# digital_sensor.net
KiCad netlist of a schematic drawn in EAGLE
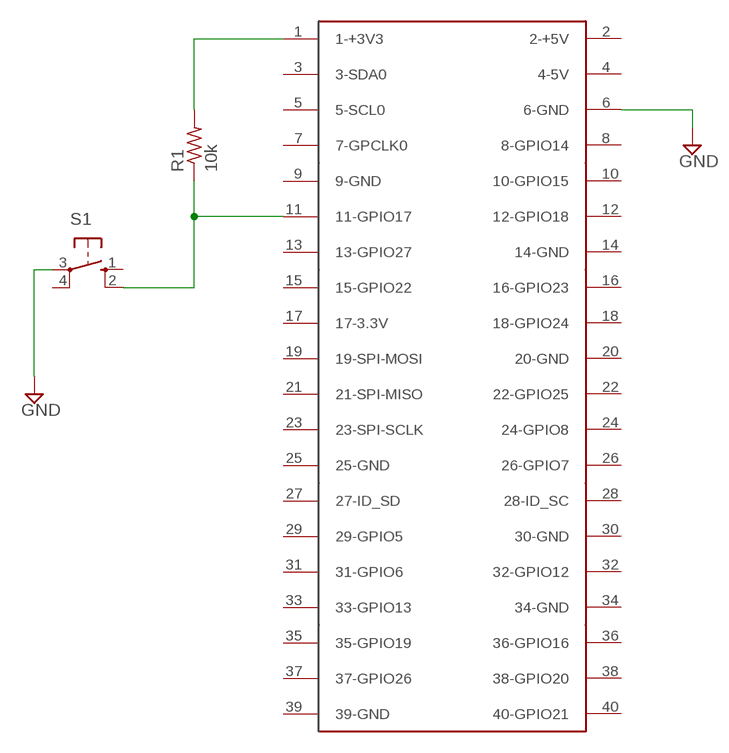
[diagram p0: schematic, sheet 1]

(export (version "E")
  (design (tool "Eeschema 10.0.6"))
  (components
    (comp (ref "R1")
      (value "10k")
      (footprint "eagle-import:0207_12")
      (libsource (lib "eagle-import") (part "R-US_0207/12"))
    )
    (comp (ref "S1")
      (value "40-XX-ROUND")
      (footprint "eagle-import:B3F-40XX-ROUND")
      (libsource (lib "eagle-import") (part "40-XX-ROUND"))
    )
    (comp (ref "U$1")
      (value "RASPBERRY-PI")
      (footprint "eagle-import:RASPBERRY-PI")
      (libsource (lib "eagle-import") (part "RASPBERRY-PI"))
    )
  )
  (nets
    (net (code "1") (name "GND") (class "Default")
      (node (ref "S1") (pin "3") (pinfunction "P_3") (pintype "passive"))
      (node (ref "U$1") (pin "6") (pinfunction "6-GND_6") (pintype "bidirectional"))
    )
    (net (code "2") (name "Net-(S1-S1)") (class "Default")
      (node (ref "R1") (pin "1") (pinfunction "1_1") (pintype "passive"))
      (node (ref "S1") (pin "2") (pinfunction "S1_2") (pintype "passive"))
      (node (ref "U$1") (pin "11") (pinfunction "11-GPIO17_11") (pintype "bidirectional"))
    )
    (net (code "3") (name "Net-(U$1-1-+3V3)") (class "Default")
      (node (ref "R1") (pin "2") (pinfunction "2_2") (pintype "passive"))
      (node (ref "U$1") (pin "1") (pinfunction "1-+3V3_1") (pintype "bidirectional"))
    )
    (net (code "4") (name "unconnected-(S1-P1-Pad4)") (class "Default")
      (node (ref "S1") (pin "4") (pinfunction "P1_4") (pintype "passive"))
    )
    (net (code "5") (name "unconnected-(S1-S-Pad1)") (class "Default")
      (node (ref "S1") (pin "1") (pinfunction "S_1") (pintype "passive"))
    )
    (net (code "6") (name "unconnected-(U$1-2-+5V-Pad2)") (class "Default")
      (node (ref "U$1") (pin "2") (pinfunction "2-+5V_2") (pintype "bidirectional"))
    )
    (net (code "7") (name "unconnected-(U$1-3-SDA0-Pad3)") (class "Default")
      (node (ref "U$1") (pin "3") (pinfunction "3-SDA0_3") (pintype "bidirectional"))
    )
    (net (code "8") (name "unconnected-(U$1-4-5V-Pad4)") (class "Default")
      (node (ref "U$1") (pin "4") (pinfunction "4-5V_4") (pintype "bidirectional"))
    )
    (net (code "9") (name "unconnected-(U$1-5-SCL0-Pad5)") (class "Default")
      (node (ref "U$1") (pin "5") (pinfunction "5-SCL0_5") (pintype "bidirectional"))
    )
    (net (code "10") (name "unconnected-(U$1-7-GPCLK0-Pad7)") (class "Default")
      (node (ref "U$1") (pin "7") (pinfunction "7-GPCLK0_7") (pintype "bidirectional"))
    )
    (net (code "11") (name "unconnected-(U$1-8-GPIO14-Pad8)") (class "Default")
      (node (ref "U$1") (pin "8") (pinfunction "8-GPIO14_8") (pintype "bidirectional"))
    )
    (net (code "12") (name "unconnected-(U$1-9-GND-Pad9)") (class "Default")
      (node (ref "U$1") (pin "9") (pinfunction "9-GND_9") (pintype "bidirectional"))
    )
    (net (code "13") (name "unconnected-(U$1-10-GPIO15-Pad10)") (class "Default")
      (node (ref "U$1") (pin "10") (pinfunction "10-GPIO15_10") (pintype "bidirectional"))
    )
    (net (code "14") (name "unconnected-(U$1-12-GPIO18-Pad12)") (class "Default")
      (node (ref "U$1") (pin "12") (pinfunction "12-GPIO18_12") (pintype "bidirectional"))
    )
    (net (code "15") (name "unconnected-(U$1-13-GPIO27-Pad13)") (class "Default")
      (node (ref "U$1") (pin "13") (pinfunction "13-GPIO27_13") (pintype "bidirectional"))
    )
    (net (code "16") (name "unconnected-(U$1-14-GND-Pad14)") (class "Default")
      (node (ref "U$1") (pin "14") (pinfunction "14-GND_14") (pintype "bidirectional"))
    )
    (net (code "17") (name "unconnected-(U$1-15-GPIO22-Pad15)") (class "Default")
      (node (ref "U$1") (pin "15") (pinfunction "15-GPIO22_15") (pintype "bidirectional"))
    )
    (net (code "18") (name "unconnected-(U$1-16-GPIO23-Pad16)") (class "Default")
      (node (ref "U$1") (pin "16") (pinfunction "16-GPIO23_16") (pintype "bidirectional"))
    )
    (net (code "19") (name "unconnected-(U$1-17-3.3V-Pad17)") (class "Default")
      (node (ref "U$1") (pin "17") (pinfunction "17-3.3V_17") (pintype "bidirectional"))
    )
    (net (code "20") (name "unconnected-(U$1-18-GPIO24-Pad18)") (class "Default")
      (node (ref "U$1") (pin "18") (pinfunction "18-GPIO24_18") (pintype "bidirectional"))
    )
    (net (code "21") (name "unconnected-(U$1-19-SPI-MOSI-Pad19)") (class "Default")
      (node (ref "U$1") (pin "19") (pinfunction "19-SPI-MOSI_19") (pintype "bidirectional"))
    )
    (net (code "22") (name "unconnected-(U$1-20-GND-Pad20)") (class "Default")
      (node (ref "U$1") (pin "20") (pinfunction "20-GND_20") (pintype "bidirectional"))
    )
    (net (code "23") (name "unconnected-(U$1-21-SPI-MISO-Pad21)") (class "Default")
      (node (ref "U$1") (pin "21") (pinfunction "21-SPI-MISO_21") (pintype "bidirectional"))
    )
    (net (code "24") (name "unconnected-(U$1-22-GPIO25-Pad22)") (class "Default")
      (node (ref "U$1") (pin "22") (pinfunction "22-GPIO25_22") (pintype "bidirectional"))
    )
    (net (code "25") (name "unconnected-(U$1-23-SPI-SCLK-Pad23)") (class "Default")
      (node (ref "U$1") (pin "23") (pinfunction "23-SPI-SCLK_23") (pintype "bidirectional"))
    )
    (net (code "26") (name "unconnected-(U$1-24-GPIO8-Pad24)") (class "Default")
      (node (ref "U$1") (pin "24") (pinfunction "24-GPIO8_24") (pintype "bidirectional"))
    )
    (net (code "27") (name "unconnected-(U$1-25-GND-Pad25)") (class "Default")
      (node (ref "U$1") (pin "25") (pinfunction "25-GND_25") (pintype "bidirectional"))
    )
    (net (code "28") (name "unconnected-(U$1-26-GPIO7-Pad26)") (class "Default")
      (node (ref "U$1") (pin "26") (pinfunction "26-GPIO7_26") (pintype "bidirectional"))
    )
    (net (code "29") (name "unconnected-(U$1-27-ID_SD-Pad27)") (class "Default")
      (node (ref "U$1") (pin "27") (pinfunction "27-ID_SD_27") (pintype "bidirectional"))
    )
    (net (code "30") (name "unconnected-(U$1-28-ID_SC-Pad28)") (class "Default")
      (node (ref "U$1") (pin "28") (pinfunction "28-ID_SC_28") (pintype "bidirectional"))
    )
    (net (code "31") (name "unconnected-(U$1-29-GPIO5-Pad29)") (class "Default")
      (node (ref "U$1") (pin "29") (pinfunction "29-GPIO5_29") (pintype "bidirectional"))
    )
    (net (code "32") (name "unconnected-(U$1-30-GND-Pad30)") (class "Default")
      (node (ref "U$1") (pin "30") (pinfunction "30-GND_30") (pintype "bidirectional"))
    )
    (net (code "33") (name "unconnected-(U$1-31-GPIO6-Pad31)") (class "Default")
      (node (ref "U$1") (pin "31") (pinfunction "31-GPIO6_31") (pintype "bidirectional"))
    )
    (net (code "34") (name "unconnected-(U$1-32-GPIO12-Pad32)") (class "Default")
      (node (ref "U$1") (pin "32") (pinfunction "32-GPIO12_32") (pintype "bidirectional"))
    )
    (net (code "35") (name "unconnected-(U$1-33-GPIO13-Pad33)") (class "Default")
      (node (ref "U$1") (pin "33") (pinfunction "33-GPIO13_33") (pintype "bidirectional"))
    )
    (net (code "36") (name "unconnected-(U$1-34-GND-Pad34)") (class "Default")
      (node (ref "U$1") (pin "34") (pinfunction "34-GND_34") (pintype "bidirectional"))
    )
    (net (code "37") (name "unconnected-(U$1-35-GPIO19-Pad35)") (class "Default")
      (node (ref "U$1") (pin "35") (pinfunction "35-GPIO19_35") (pintype "bidirectional"))
    )
    (net (code "38") (name "unconnected-(U$1-36-GPIO16-Pad36)") (class "Default")
      (node (ref "U$1") (pin "36") (pinfunction "36-GPIO16_36") (pintype "bidirectional"))
    )
    (net (code "39") (name "unconnected-(U$1-37-GPIO26-Pad37)") (class "Default")
      (node (ref "U$1") (pin "37") (pinfunction "37-GPIO26_37") (pintype "bidirectional"))
    )
    (net (code "40") (name "unconnected-(U$1-38-GPIO20-Pad38)") (class "Default")
      (node (ref "U$1") (pin "38") (pinfunction "38-GPIO20_38") (pintype "bidirectional"))
    )
    (net (code "41") (name "unconnected-(U$1-39-GND-Pad39)") (class "Default")
      (node (ref "U$1") (pin "39") (pinfunction "39-GND_39") (pintype "bidirectional"))
    )
    (net (code "42") (name "unconnected-(U$1-40-GPIO21-Pad40)") (class "Default")
      (node (ref "U$1") (pin "40") (pinfunction "40-GPIO21_40") (pintype "bidirectional"))
    )
  )
)
